# HV-Trigger.net
KiCad netlist of a schematic drawn in Altium Designer
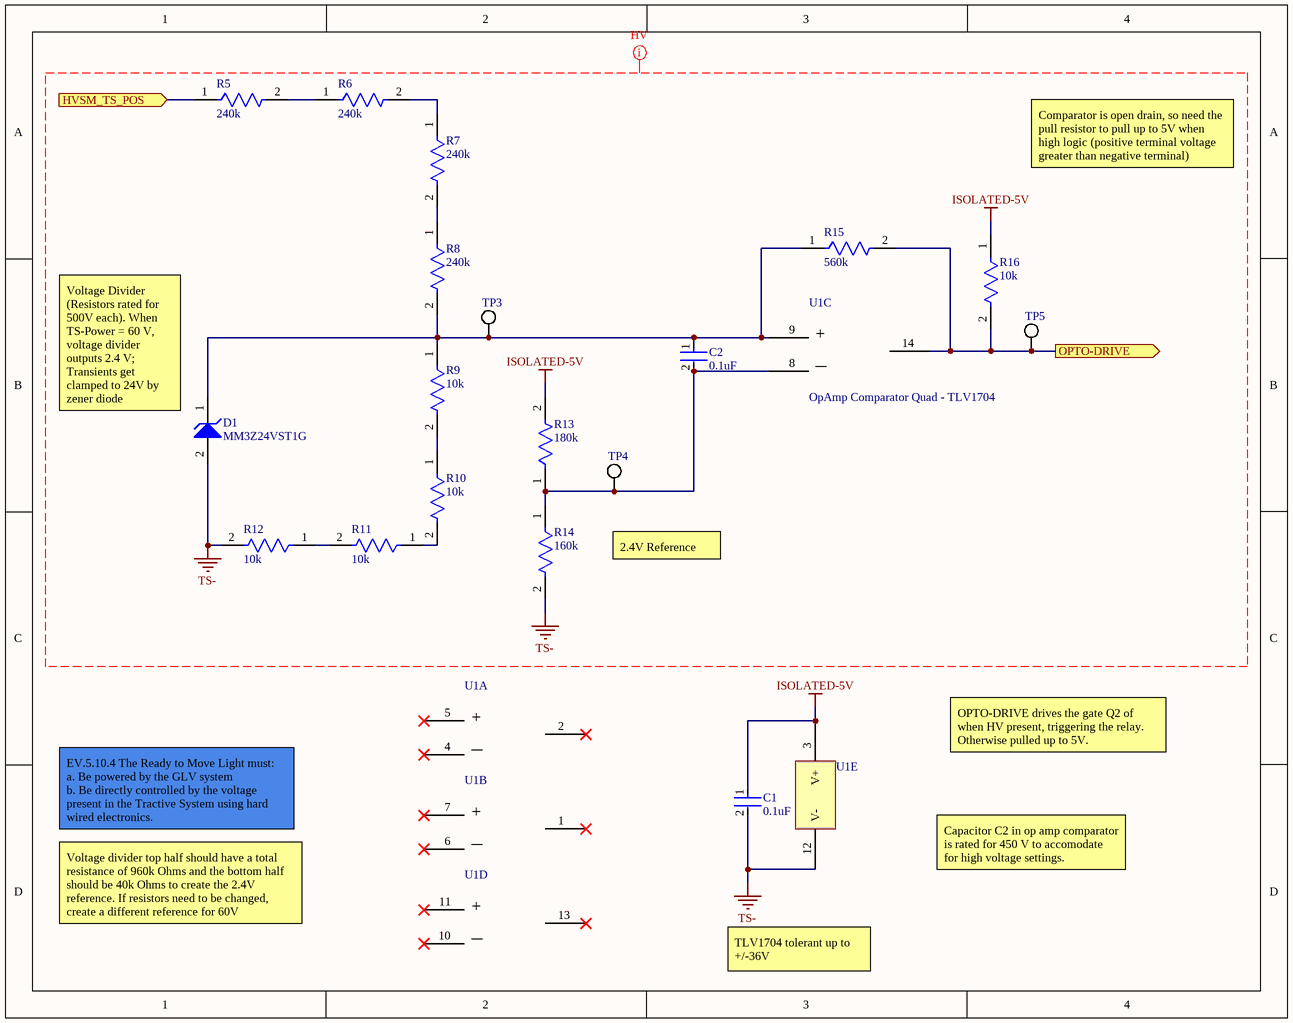
[diagram p0: HV-Trigger.SchDoc]

(export (version "E")
  (design (tool "Eeschema 10.0.6"))
  (components
    (comp (ref "C1")
      (value "0.1uF")
      (footprint "FP-C1206C-EB-MFG")
      (description "CAP CER 0.1UF 250V X7R 1206")
      (fields
        (field (name "MANUFACTURER PART NUMBER") "C1206C104KARACTU")
        (field (name "MANUFACTURER") "KEMET")
      )
      (libsource (lib "Altium Content Vault") (part "b4654b650e69147ec39a6b967a45e02"))
    )
    (comp (ref "C2")
      (value "0.1uF")
      (footprint "FP-CGA5L-0_3-0_1-IPC_B")
      (description "Cap Ceramic 100nF 450V X7T 10% Pad SMD 1206 +125°C Automotive T/R")
      (fields (field (name "TOLERANCE") "10%"))
      (libsource (lib "Altium Content Vault") (part "b4654b650e69147ec39a6b967a45e02"))
    )
    (comp (ref "D1")
      (value "MM3Z24VST1G")
      (footprint "ONSC-SOD-323-2-477-02_V")
      (description "Zener Voltage Regulator, 300 mW, 2-Pin SOD-323, Pb-Free, Tape and Reel")
      (fields (field (name "MANUFACTURER") "On Semiconductor") (field (name "PARTNUMBER") "MM3Z36VT1G"))
      (libsource (lib "Altium Content Vault") (part "ONSC-K1A2-2"))
    )
    (comp (ref "R5")
      (value "240k")
      (footprint "FP-KTR18-IPC_A")
      (description "Res Thick Film 1206 240kΩ 1% 0.1W ±100ppm/°C Automotive Paper T/R")
      (fields (field (name "TOLERANCE") "1%"))
      (libsource (lib "Altium Content Vault") (part "1029c3af85768c4190bb7ad29bc67b5"))
    )
    (comp (ref "R6")
      (value "240k")
      (footprint "FP-KTR18-IPC_A")
      (description "Res Thick Film 1206 240kΩ 1% 0.1W ±100ppm/°C Automotive Paper T/R")
      (fields (field (name "TOLERANCE") "1%"))
      (libsource (lib "Altium Content Vault") (part "1029c3af85768c4190bb7ad29bc67b5"))
    )
    (comp (ref "R7")
      (value "240k")
      (footprint "FP-KTR18-IPC_A")
      (description "Res Thick Film 1206 240kΩ 1% 0.1W ±100ppm/°C Automotive Paper T/R")
      (fields (field (name "TOLERANCE") "1%"))
      (libsource (lib "Altium Content Vault") (part "1029c3af85768c4190bb7ad29bc67b5"))
    )
    (comp (ref "R8")
      (value "240k")
      (footprint "FP-KTR18-IPC_A")
      (description "Res Thick Film 1206 240kΩ 1% 0.1W ±100ppm/°C Automotive Paper T/R")
      (fields (field (name "TOLERANCE") "1%"))
      (libsource (lib "Altium Content Vault") (part "1029c3af85768c4190bb7ad29bc67b5"))
    )
    (comp (ref "R9")
      (value "10k")
      (footprint "FP-KTR18-MFG")
      (description "Res Thick Film 1206 10kΩ 1% 0.1W ±100ppm/°C Automotive Paper T/R")
      (fields (field (name "TOLERANCE") "1%") (field (name "MANUFACTURER") "Rohm"))
      (libsource (lib "Altium Content Vault") (part "1029c3af85768c4190bb7ad29bc67b5"))
    )
    (comp (ref "R10")
      (value "10k")
      (footprint "FP-KTR18-MFG")
      (description "Res Thick Film 1206 10kΩ 1% 0.1W ±100ppm/°C Automotive Paper T/R")
      (fields (field (name "TOLERANCE") "1%") (field (name "MANUFACTURER") "Rohm"))
      (libsource (lib "Altium Content Vault") (part "1029c3af85768c4190bb7ad29bc67b5"))
    )
    (comp (ref "R11")
      (value "10k")
      (footprint "FP-KTR18-MFG")
      (description "Res Thick Film 1206 10kΩ 1% 0.1W ±100ppm/°C Automotive Paper T/R")
      (fields (field (name "TOLERANCE") "1%"))
      (libsource (lib "Altium Content Vault") (part "1029c3af85768c4190bb7ad29bc67b5"))
    )
    (comp (ref "R12")
      (value "10k")
      (footprint "FP-KTR18-MFG")
      (description "Res Thick Film 1206 10kΩ 1% 0.1W ±100ppm/°C Automotive Paper T/R")
      (fields (field (name "TOLERANCE") "1%"))
      (libsource (lib "Altium Content Vault") (part "1029c3af85768c4190bb7ad29bc67b5"))
    )
    (comp (ref "R13")
      (value "180k")
      (footprint "FP-KTR18-MFG")
      (description "Res Thick Film 1206 180kΩ 1% 0.1W ±100ppm/°C Automotive Paper T/R")
      (fields (field (name "TOLERANCE") "1%"))
      (libsource (lib "Altium Content Vault") (part "1029c3af85768c4190bb7ad29bc67b5"))
    )
    (comp (ref "R14")
      (value "160k")
      (footprint "FP-KTR18-IPC_C")
      (description "Res Thick Film 1206 160kΩ 1% 0.1W ±100ppm/°C Automotive Paper T/R")
      (fields (field (name "TOLERANCE") "1%"))
      (libsource (lib "Altium Content Vault") (part "1029c3af85768c4190bb7ad29bc67b5"))
    )
    (comp (ref "R15")
      (value "560k")
      (footprint "FP-KTR18-IPC_C")
      (description "Res Thick Film 1206 560kΩ 1% 0.1W ±100ppm/°C Automotive Paper T/R")
      (fields (field (name "TOLERANCE") "1%"))
      (libsource (lib "Altium Content Vault") (part "1029c3af85768c4190bb7ad29bc67b5"))
    )
    (comp (ref "R16")
      (value "10k")
      (footprint "FP-KTR18-MFG")
      (description "Res Thick Film 1206 10kΩ 1% 0.1W ±100ppm/°C Automotive Paper T/R")
      (fields (field (name "TOLERANCE") "1%"))
      (libsource (lib "Altium Content Vault") (part "1029c3af85768c4190bb7ad29bc67b5"))
    )
    (comp (ref "TP3")
      (value "~")
      (footprint "FOOTPRINT-GENERIC-TP-VIA-1MM")
      (libsource (lib "University of California Riverside - FSAE") (part "Misc-Generic-TP"))
    )
    (comp (ref "TP4")
      (value "~")
      (footprint "FOOTPRINT-GENERIC-TP-VIA-1MM")
      (libsource (lib "University of California Riverside - FSAE") (part "Misc-Generic-TP"))
    )
    (comp (ref "TP5")
      (value "~")
      (footprint "FOOTPRINT-GENERIC-TP-VIA-1MM")
      (libsource (lib "University of California Riverside - FSAE") (part "Misc-Generic-TP"))
    )
    (comp (ref "U1")
      (value "OpAmp Comparator Quad - TLV1704")
      (footprint "TSOP65P640X120-14N")
      (description "IC COMPARATOR QUAD 14TSSOP")
      (libsource (lib "University of California Riverside - FSAE") (part "TLV1704"))
    )
  )
  (nets
    (net (code "1") (name "/HVSM_TS_POS") (class "Default")
      (node (ref "R5") (pin "1") (pinfunction "1_1") (pintype "passive"))
    )
    (net (code "2") (name "/OPTO-DRIVE") (class "Default")
      (node (ref "R15") (pin "2") (pinfunction "2_2") (pintype "passive"))
      (node (ref "R16") (pin "2") (pinfunction "2_2") (pintype "passive"))
      (node (ref "TP5") (pin "1") (pinfunction "TP_1") (pintype "passive"))
      (node (ref "U1") (pin "14") (pinfunction "3OUT_14") (pintype "passive"))
    )
    (net (code "3") (name "ISOLATED-5V") (class "Default")
      (node (ref "C1") (pin "1") (pinfunction "1_1") (pintype "passive"))
      (node (ref "R13") (pin "2") (pinfunction "2_2") (pintype "passive"))
      (node (ref "R16") (pin "1") (pinfunction "1_1") (pintype "passive"))
      (node (ref "U1") (pin "3") (pinfunction "V+_3") (pintype "passive"))
    )
    (net (code "4") (name "Net-(D1-K)") (class "Default")
      (node (ref "C2") (pin "1") (pinfunction "1_1") (pintype "passive"))
      (node (ref "D1") (pin "1") (pinfunction "K_1") (pintype "passive"))
      (node (ref "R15") (pin "1") (pinfunction "1_1") (pintype "passive"))
      (node (ref "R8") (pin "2") (pinfunction "2_2") (pintype "passive"))
      (node (ref "R9") (pin "1") (pinfunction "1_1") (pintype "passive"))
      (node (ref "TP3") (pin "1") (pinfunction "TP_1") (pintype "passive"))
      (node (ref "U1") (pin "9") (pinfunction "3IN+_9") (pintype "passive"))
    )
    (net (code "5") (name "Net-(R5-Pad2)") (class "Default")
      (node (ref "R5") (pin "2") (pinfunction "2_2") (pintype "passive"))
      (node (ref "R6") (pin "1") (pinfunction "1_1") (pintype "passive"))
    )
    (net (code "6") (name "Net-(R6-Pad2)") (class "Default")
      (node (ref "R6") (pin "2") (pinfunction "2_2") (pintype "passive"))
      (node (ref "R7") (pin "1") (pinfunction "1_1") (pintype "passive"))
    )
    (net (code "7") (name "Net-(R7-Pad2)") (class "Default")
      (node (ref "R7") (pin "2") (pinfunction "2_2") (pintype "passive"))
      (node (ref "R8") (pin "1") (pinfunction "1_1") (pintype "passive"))
    )
    (net (code "8") (name "Net-(R10-Pad1)") (class "Default")
      (node (ref "R10") (pin "1") (pinfunction "1_1") (pintype "passive"))
      (node (ref "R9") (pin "2") (pinfunction "2_2") (pintype "passive"))
    )
    (net (code "9") (name "Net-(R10-Pad2)") (class "Default")
      (node (ref "R10") (pin "2") (pinfunction "2_2") (pintype "passive"))
      (node (ref "R11") (pin "1") (pinfunction "1_1") (pintype "passive"))
    )
    (net (code "10") (name "Net-(R11-Pad2)") (class "Default")
      (node (ref "R11") (pin "2") (pinfunction "2_2") (pintype "passive"))
      (node (ref "R12") (pin "1") (pinfunction "1_1") (pintype "passive"))
    )
    (net (code "11") (name "Net-(TP4-TP)") (class "Default")
      (node (ref "C2") (pin "2") (pinfunction "2_2") (pintype "passive"))
      (node (ref "R13") (pin "1") (pinfunction "1_1") (pintype "passive"))
      (node (ref "R14") (pin "1") (pinfunction "1_1") (pintype "passive"))
      (node (ref "TP4") (pin "1") (pinfunction "TP_1") (pintype "passive"))
      (node (ref "U1") (pin "8") (pinfunction "3IN-_8") (pintype "passive"))
    )
    (net (code "12") (name "TS-") (class "Default")
      (node (ref "C1") (pin "2") (pinfunction "2_2") (pintype "passive"))
      (node (ref "D1") (pin "2") (pinfunction "A_2") (pintype "passive"))
      (node (ref "R12") (pin "2") (pinfunction "2_2") (pintype "passive"))
      (node (ref "R14") (pin "2") (pinfunction "2_2") (pintype "passive"))
      (node (ref "U1") (pin "12") (pinfunction "V-_12") (pintype "passive"))
    )
    (net (code "13") (name "unconnected-(U1A-1IN+-Pad5)") (class "Default")
      (node (ref "U1") (pin "5") (pinfunction "1IN+_5") (pintype "passive+no_connect"))
    )
    (net (code "14") (name "unconnected-(U1A-1IN--Pad4)") (class "Default")
      (node (ref "U1") (pin "4") (pinfunction "1IN-_4") (pintype "passive+no_connect"))
    )
    (net (code "15") (name "unconnected-(U1A-1OUT-Pad2)") (class "Default")
      (node (ref "U1") (pin "2") (pinfunction "1OUT_2") (pintype "passive+no_connect"))
    )
    (net (code "16") (name "unconnected-(U1B-2IN+-Pad7)") (class "Default")
      (node (ref "U1") (pin "7") (pinfunction "2IN+_7") (pintype "passive+no_connect"))
    )
    (net (code "17") (name "unconnected-(U1B-2N--Pad6)") (class "Default")
      (node (ref "U1") (pin "6") (pinfunction "2N-_6") (pintype "passive+no_connect"))
    )
    (net (code "18") (name "unconnected-(U1B-2OUT-Pad1)") (class "Default")
      (node (ref "U1") (pin "1") (pinfunction "2OUT_1") (pintype "passive+no_connect"))
    )
    (net (code "19") (name "unconnected-(U1D-4IN+-Pad11)") (class "Default")
      (node (ref "U1") (pin "11") (pinfunction "4IN+_11") (pintype "passive+no_connect"))
    )
    (net (code "20") (name "unconnected-(U1D-4IN--Pad10)") (class "Default")
      (node (ref "U1") (pin "10") (pinfunction "4IN-_10") (pintype "passive+no_connect"))
    )
    (net (code "21") (name "unconnected-(U1D-4OUT-Pad13)") (class "Default")
      (node (ref "U1") (pin "13") (pinfunction "4OUT_13") (pintype "passive+no_connect"))
    )
  )
)
